# final.net
KiCad netlist of a schematic drawn in EasyEDA Pro
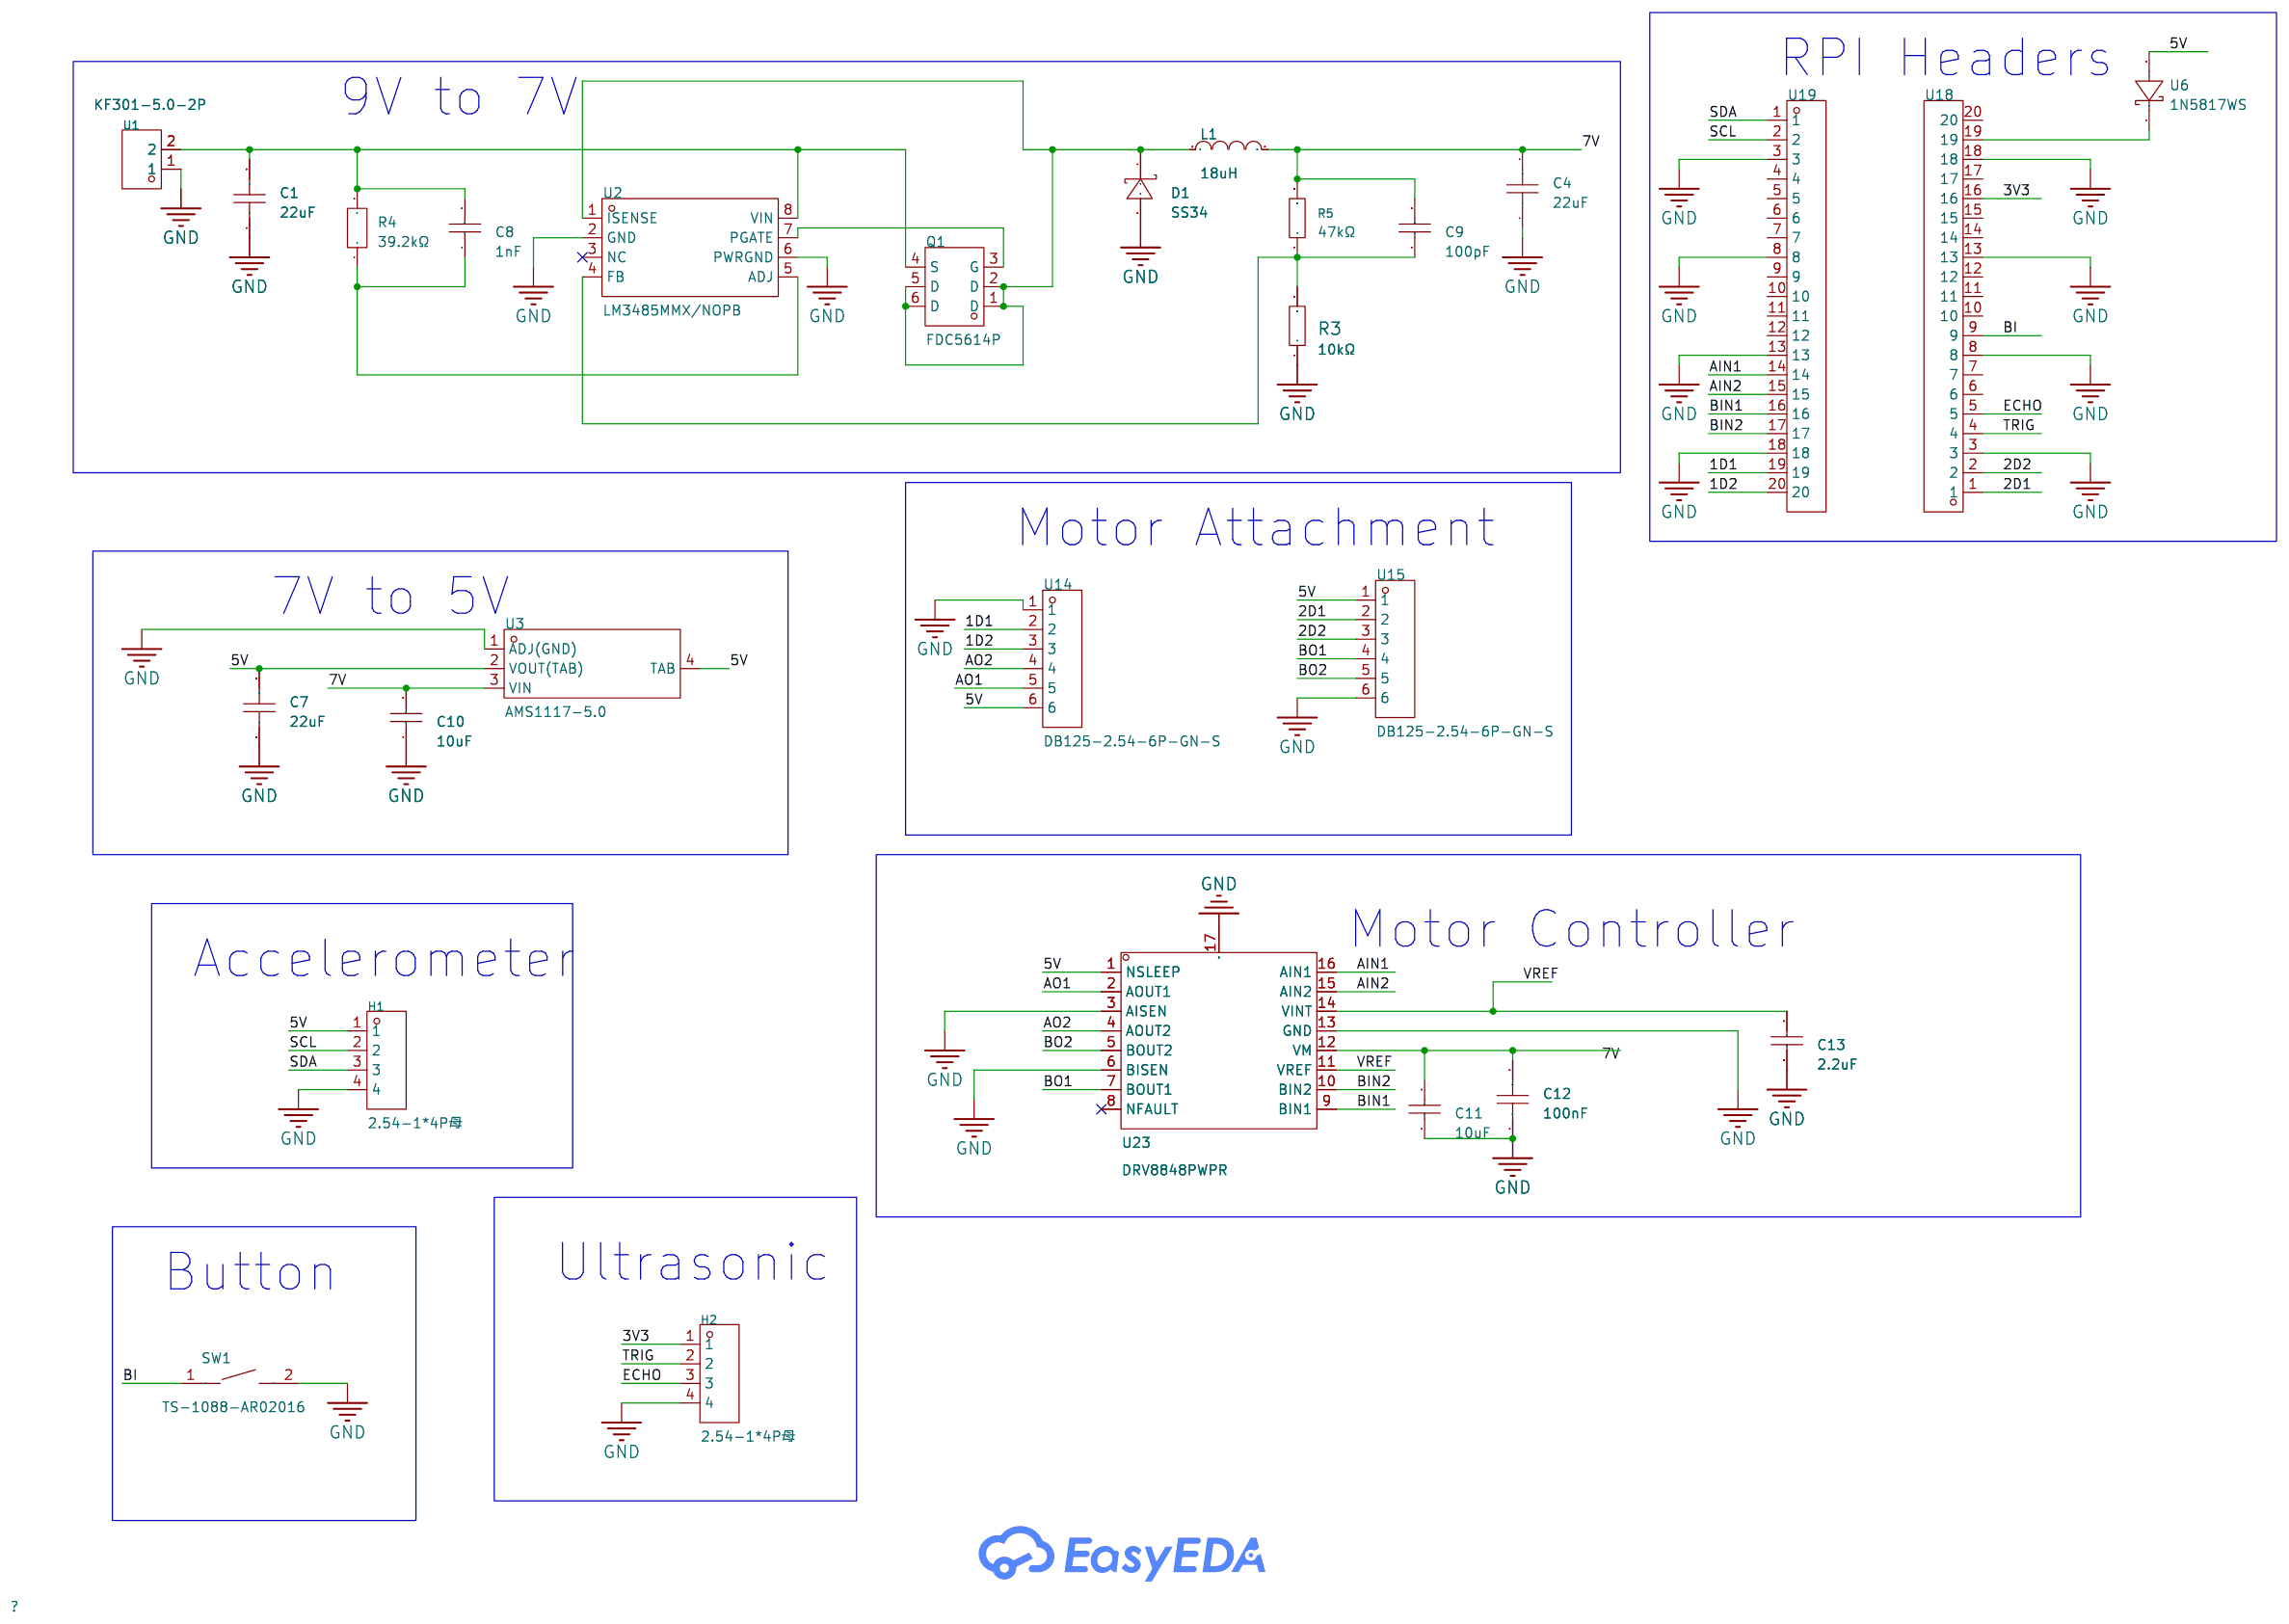
[diagram p0: schematic sheet]

(export (version "E")
  (design (tool "Eeschema 10.0.6"))
  (components
    (comp (ref "C1")
      (value "22uF")
      (footprint "easyedapro:C0603")
      (description "Capacitance:22uF Tolerance:±20% Tolerance:±20% Voltage Rating:6.3V Temperature Coefficient:X5R")
      (fields
        (field (name "Manufacturer Part") "CL10A226MQ8NRNC")
        (field (name "Manufacturer") "SAMSUNG(三星)")
      )
      (libsource (lib "easyedapro") (part "CL10A226MQ8NRNC"))
    )
    (comp (ref "C4")
      (value "22uF")
      (footprint "easyedapro:C0603")
      (description "Capacitance:22uF Tolerance:±20% Tolerance:±20% Voltage Rating:6.3V Temperature Coefficient:X5R")
      (fields
        (field (name "Manufacturer Part") "CL10A226MQ8NRNC")
        (field (name "Manufacturer") "SAMSUNG(三星)")
      )
      (libsource (lib "easyedapro") (part "CL10A226MQ8NRNC"))
    )
    (comp (ref "C7")
      (value "22uF")
      (footprint "easyedapro:C0603")
      (description "Capacitance:22uF Tolerance:±20% Tolerance:±20% Voltage Rating:6.3V Temperature Coefficient:X5R")
      (fields
        (field (name "Manufacturer Part") "CL10A226MQ8NRNC")
        (field (name "Manufacturer") "SAMSUNG(三星)")
      )
      (libsource (lib "easyedapro") (part "CL10A226MQ8NRNC"))
    )
    (comp (ref "C8")
      (value "1nF")
      (footprint "easyedapro:C0402")
      (description "Capacitance:1nF Tolerance:±10% Tolerance:±10% Voltage Rating:50V Temperature Coefficient:X7R")
      (fields (field (name "Manufacturer Part") "0402B102K500NT") (field (name "Manufacturer") "FH(风华)"))
      (libsource (lib "easyedapro") (part "0402B102K500NT"))
    )
    (comp (ref "C9")
      (value "100pF")
      (footprint "easyedapro:C0402")
      (fields (field (name "Manufacturer Part") "0402CG101J500NT") (field (name "Manufacturer") "FH(风华)"))
      (libsource (lib "easyedapro") (part "0402CG101J500NT"))
    )
    (comp (ref "C10")
      (value "10uF")
      (footprint "easyedapro:C1206")
      (description "Capacitance:10uF Tolerance:±10% Tolerance:±10% Voltage Rating:50V Temperature Coefficient:X5R")
      (fields
        (field (name "Manufacturer Part") "CL31A106KBHNNNE")
        (field (name "Manufacturer") "SAMSUNG(三星)")
      )
      (libsource (lib "easyedapro") (part "CL31A106KBHNNNE"))
    )
    (comp (ref "C11")
      (value "10uF")
      (footprint "easyedapro:C1206")
      (description "Capacitance:10uF Tolerance:±10% Tolerance:±10% Voltage Rating:50V Temperature Coefficient:X5R")
      (fields
        (field (name "Manufacturer Part") "CL31A106KBHNNNE")
        (field (name "Manufacturer") "SAMSUNG(三星)")
      )
      (libsource (lib "easyedapro") (part "CL31A106KBHNNNE"))
    )
    (comp (ref "C12")
      (value "100nF")
      (footprint "easyedapro:C0402")
      (description "Capacitance:100nF Tolerance:±10% Tolerance:±10% Voltage Rating:16V Temperature Coefficient:X7R")
      (fields
        (field (name "Manufacturer Part") "CL05B104KO5NNNC")
        (field (name "Manufacturer") "SAMSUNG(三星)")
      )
      (libsource (lib "easyedapro") (part "CL05B104KO5NNNC"))
    )
    (comp (ref "C13")
      (value "2.2uF")
      (footprint "easyedapro:C0603")
      (description "Capacitance:2.2uF Tolerance:±10% Tolerance:±10% Voltage Rating:16V Temperature Coefficient:X5R")
      (fields
        (field (name "Manufacturer Part") "CL10A225KO8NNNC")
        (field (name "Manufacturer") "SAMSUNG(三星)")
      )
      (libsource (lib "easyedapro") (part "CL10A225KO8NNNC"))
    )
    (comp (ref "D1")
      (value "SS34")
      (footprint "easyedapro:SMA_L4.3-W2.6-LS5.2-RD")
      (fields (field (name "Manufacturer") "MDD(辰达半导体)"))
      (libsource (lib "easyedapro") (part "SS34_C8678"))
    )
    (comp (ref "H1")
      (value "2.54-1*4P母")
      (footprint "easyedapro:HDR-TH_4P-P2.54-V-F")
      (fields (field (name "Manufacturer") "BOOMELE(博穆精密)"))
      (libsource (lib "easyedapro") (part "2.54-1*4P母"))
    )
    (comp (ref "H2")
      (value "2.54-1*4P母")
      (footprint "easyedapro:HDR-TH_4P-P2.54-V-F")
      (fields (field (name "Manufacturer") "BOOMELE(博穆精密)"))
      (libsource (lib "easyedapro") (part "2.54-1*4P母"))
    )
    (comp (ref "L1")
      (value "18uH")
      (footprint "easyedapro:IND-SMD_L4.0-W4.0_FNR4012S")
      (fields (field (name "Manufacturer Part") "FNR4012S180MT") (field (name "Manufacturer") "cjiang(长江微电)"))
      (libsource (lib "easyedapro") (part "FNR4012S180MT"))
    )
    (comp (ref "Q1")
      (value "FDC5614P")
      (footprint "easyedapro:SOT-23-6_L2.9-W1.6-P0.95-LS2.8-BR")
      (fields (field (name "Manufacturer") "MSKSEMI(美森科)"))
      (libsource (lib "easyedapro") (part "FDC5614P_C3029022"))
    )
    (comp (ref "R3")
      (value "10kΩ")
      (footprint "easyedapro:R0603")
      (fields
        (field (name "Manufacturer Part") "0603WAF1002T5E")
        (field (name "Manufacturer") "UNI-ROYAL(厚声)")
      )
      (libsource (lib "easyedapro") (part "0603WAF1002T5E"))
    )
    (comp (ref "R4")
      (value "39.2kΩ")
      (footprint "easyedapro:R0402")
      (fields (field (name "Manufacturer Part") "FRC0402F3922TS") (field (name "Manufacturer") "FOJAN(富捷)"))
      (libsource (lib "easyedapro") (part "FRC0402F3922TS"))
    )
    (comp (ref "R5")
      (value "47kΩ")
      (footprint "easyedapro:R0805")
      (fields
        (field (name "Manufacturer Part") "0805W8F4702T5E")
        (field (name "Manufacturer") "UNI-ROYAL(厚声)")
      )
      (libsource (lib "easyedapro") (part "0805W8F4702T5E"))
    )
    (comp (ref "SW1")
      (value "TS-1088-AR02016")
      (footprint "easyedapro:SW-SMD_L3.9-W3.0-P4.45")
      (fields (field (name "Manufacturer") "XUNPU(讯普)"))
      (libsource (lib "easyedapro") (part "TS-1088-AR02016"))
    )
    (comp (ref "U1")
      (value "KF301-5.0-2P")
      (footprint "easyedapro:CONN-TH_P5.00_KF301-5.0-2P")
      (fields (field (name "Manufacturer") "KEFA(科发)"))
      (libsource (lib "easyedapro") (part "KF301-5.0-2P"))
    )
    (comp (ref "U2")
      (value "LM3485MMX/NOPB")
      (footprint "easyedapro:VSSOP-8_L3.0-W3.0-P0.65-LS4.9-BL")
      (fields (field (name "Manufacturer") "TI(德州仪器)"))
      (libsource (lib "easyedapro") (part "LM3485MMX/NOPB"))
    )
    (comp (ref "U3")
      (value "AMS1117-5.0")
      (footprint "easyedapro:SOT-223_L6.7-W3.5-P2.30-BR")
      (fields (field (name "Manufacturer") "UMW(友台半导体)"))
      (libsource (lib "easyedapro") (part "AMS1117-5.0_C347223"))
    )
    (comp (ref "U6")
      (value "1N5817WS")
      (footprint "easyedapro:SOD-323_L1.7-W1.3-LS2.6-RD-1")
      (description "Reverse Voltage (Vr):20V Rectified Current:1A")
      (fields (field (name "Manufacturer") "Hottech(合科泰)"))
      (libsource (lib "easyedapro") (part "1N5817WS_C5190152"))
    )
    (comp (ref "U14")
      (value "DB125-2.54-6P-GN-S")
      (footprint "easyedapro:CONN-TH_DB125-2.54-6P-GN")
      (fields (field (name "Manufacturer") "DORABO(地博电气)"))
      (libsource (lib "easyedapro") (part "DB125-2.54-6P-GN"))
    )
    (comp (ref "U15")
      (value "DB125-2.54-6P-GN-S")
      (footprint "easyedapro:CONN-TH_DB125-2.54-6P-GN")
      (fields (field (name "Manufacturer") "DORABO(地博电气)"))
      (libsource (lib "easyedapro") (part "DB125-2.54-6P-GN"))
    )
    (comp (ref "U18")
      (value "ZX-PM2.54-1-20PY")
      (footprint "easyedapro:HDR-TH_20P-P2.54-V-F")
      (fields (field (name "Manufacturer") "Megastar(兆星)"))
      (libsource (lib "easyedapro") (part "ZX-PM2.54-1-20PY"))
    )
    (comp (ref "U19")
      (value "ZX-PM2.54-1-20PY")
      (footprint "easyedapro:HDR-TH_20P-P2.54-V-F")
      (fields (field (name "Manufacturer") "Megastar(兆星)"))
      (libsource (lib "easyedapro") (part "ZX-PM2.54-1-20PY"))
    )
    (comp (ref "U23")
      (value "DRV8848PWPR")
      (footprint "easyedapro:HTSSOP-16_L5.0-W4.4-P0.65-LS6.4-BL-EP")
      (fields (field (name "Manufacturer") "TI(德州仪器)"))
      (libsource (lib "easyedapro") (part "DRV8848PWPR"))
    )
  )
  (nets
    (net (code "1") (name "/1D1") (class "Default")
      (node (ref "U14") (pin "2") (pinfunction "2_2") (pintype "unspecified"))
      (node (ref "U19") (pin "19") (pinfunction "19_19") (pintype "unspecified"))
    )
    (net (code "2") (name "/1D2") (class "Default")
      (node (ref "U14") (pin "3") (pinfunction "3_3") (pintype "unspecified"))
      (node (ref "U19") (pin "20") (pinfunction "20_20") (pintype "unspecified"))
    )
    (net (code "3") (name "/2D1") (class "Default")
      (node (ref "U15") (pin "2") (pinfunction "2_2") (pintype "unspecified"))
      (node (ref "U18") (pin "1") (pinfunction "1_1") (pintype "unspecified"))
    )
    (net (code "4") (name "/2D2") (class "Default")
      (node (ref "U15") (pin "3") (pinfunction "3_3") (pintype "unspecified"))
      (node (ref "U18") (pin "2") (pinfunction "2_2") (pintype "unspecified"))
    )
    (net (code "5") (name "/3V3") (class "Default")
      (node (ref "H2") (pin "1") (pinfunction "1_1") (pintype "input"))
      (node (ref "U18") (pin "16") (pinfunction "16_16") (pintype "unspecified"))
    )
    (net (code "6") (name "/5V") (class "Default")
      (node (ref "C7") (pin "2") (pinfunction "2_2") (pintype "unspecified"))
      (node (ref "H1") (pin "1") (pinfunction "1_1") (pintype "input"))
      (node (ref "U14") (pin "6") (pinfunction "6_6") (pintype "unspecified"))
      (node (ref "U15") (pin "1") (pinfunction "1_1") (pintype "unspecified"))
      (node (ref "U23") (pin "1") (pinfunction "NSLEEP_1") (pintype "unspecified"))
      (node (ref "U3") (pin "2") (pinfunction "VOUT(TAB)_2") (pintype "unspecified"))
      (node (ref "U3") (pin "4") (pinfunction "TAB_4") (pintype "unspecified"))
      (node (ref "U6") (pin "2") (pinfunction "A_2") (pintype "unspecified"))
    )
    (net (code "7") (name "/7V") (class "Default")
      (node (ref "C10") (pin "2") (pinfunction "2_2") (pintype "input"))
      (node (ref "C11") (pin "2") (pinfunction "2_2") (pintype "input"))
      (node (ref "C12") (pin "2") (pinfunction "2_2") (pintype "unspecified"))
      (node (ref "C4") (pin "2") (pinfunction "2_2") (pintype "unspecified"))
      (node (ref "C9") (pin "2") (pinfunction "2_2") (pintype "input"))
      (node (ref "L1") (pin "2") (pinfunction "2_2") (pintype "unspecified"))
      (node (ref "R5") (pin "2") (pinfunction "2_2") (pintype "input"))
      (node (ref "U23") (pin "12") (pinfunction "VM_12") (pintype "unspecified"))
      (node (ref "U3") (pin "3") (pinfunction "VIN_3") (pintype "unspecified"))
    )
    (net (code "8") (name "/AIN1") (class "Default")
      (node (ref "U19") (pin "14") (pinfunction "14_14") (pintype "unspecified"))
      (node (ref "U23") (pin "16") (pinfunction "AIN1_16") (pintype "unspecified"))
    )
    (net (code "9") (name "/AIN2") (class "Default")
      (node (ref "U19") (pin "15") (pinfunction "15_15") (pintype "unspecified"))
      (node (ref "U23") (pin "15") (pinfunction "AIN2_15") (pintype "unspecified"))
    )
    (net (code "10") (name "/AO1") (class "Default")
      (node (ref "U14") (pin "5") (pinfunction "5_5") (pintype "unspecified"))
      (node (ref "U23") (pin "2") (pinfunction "AOUT1_2") (pintype "unspecified"))
    )
    (net (code "11") (name "/AO2") (class "Default")
      (node (ref "U14") (pin "4") (pinfunction "4_4") (pintype "unspecified"))
      (node (ref "U23") (pin "4") (pinfunction "AOUT2_4") (pintype "unspecified"))
    )
    (net (code "12") (name "/BI") (class "Default")
      (node (ref "SW1") (pin "1") (pinfunction "1_1") (pintype "unspecified"))
      (node (ref "U18") (pin "9") (pinfunction "9_9") (pintype "unspecified"))
    )
    (net (code "13") (name "/BIN1") (class "Default")
      (node (ref "U19") (pin "16") (pinfunction "16_16") (pintype "unspecified"))
      (node (ref "U23") (pin "9") (pinfunction "BIN1_9") (pintype "unspecified"))
    )
    (net (code "14") (name "/BIN2") (class "Default")
      (node (ref "U19") (pin "17") (pinfunction "17_17") (pintype "unspecified"))
      (node (ref "U23") (pin "10") (pinfunction "BIN2_10") (pintype "unspecified"))
    )
    (net (code "15") (name "/BO1") (class "Default")
      (node (ref "U15") (pin "4") (pinfunction "4_4") (pintype "unspecified"))
      (node (ref "U23") (pin "7") (pinfunction "BOUT1_7") (pintype "unspecified"))
    )
    (net (code "16") (name "/BO2") (class "Default")
      (node (ref "U15") (pin "5") (pinfunction "5_5") (pintype "unspecified"))
      (node (ref "U23") (pin "5") (pinfunction "BOUT2_5") (pintype "unspecified"))
    )
    (net (code "17") (name "/ECHO") (class "Default")
      (node (ref "H2") (pin "3") (pinfunction "3_3") (pintype "input"))
      (node (ref "U18") (pin "5") (pinfunction "5_5") (pintype "unspecified"))
    )
    (net (code "18") (name "/SCL") (class "Default")
      (node (ref "H1") (pin "2") (pinfunction "2_2") (pintype "input"))
      (node (ref "U19") (pin "2") (pinfunction "2_2") (pintype "unspecified"))
    )
    (net (code "19") (name "/SDA") (class "Default")
      (node (ref "H1") (pin "3") (pinfunction "3_3") (pintype "input"))
      (node (ref "U19") (pin "1") (pinfunction "1_1") (pintype "unspecified"))
    )
    (net (code "20") (name "/TRIG") (class "Default")
      (node (ref "H2") (pin "2") (pinfunction "2_2") (pintype "input"))
      (node (ref "U18") (pin "4") (pinfunction "4_4") (pintype "unspecified"))
    )
    (net (code "21") (name "/VREF") (class "Default")
      (node (ref "C13") (pin "2") (pinfunction "2_2") (pintype "input"))
      (node (ref "U23") (pin "11") (pinfunction "VREF_11") (pintype "unspecified"))
      (node (ref "U23") (pin "14") (pinfunction "VINT_14") (pintype "unspecified"))
    )
    (net (code "22") (name "GND") (class "Default")
      (node (ref "C1") (pin "1") (pinfunction "1_1") (pintype "unspecified"))
      (node (ref "C10") (pin "1") (pinfunction "1_1") (pintype "input"))
      (node (ref "C11") (pin "1") (pinfunction "1_1") (pintype "input"))
      (node (ref "C12") (pin "1") (pinfunction "1_1") (pintype "unspecified"))
      (node (ref "C13") (pin "1") (pinfunction "1_1") (pintype "input"))
      (node (ref "C4") (pin "1") (pinfunction "1_1") (pintype "unspecified"))
      (node (ref "C7") (pin "1") (pinfunction "1_1") (pintype "unspecified"))
      (node (ref "D1") (pin "2") (pinfunction "A_2") (pintype "unspecified"))
      (node (ref "H1") (pin "4") (pinfunction "4_4") (pintype "input"))
      (node (ref "H2") (pin "4") (pinfunction "4_4") (pintype "input"))
      (node (ref "R3") (pin "1") (pinfunction "1_1") (pintype "input"))
      (node (ref "SW1") (pin "2") (pinfunction "2_2") (pintype "unspecified"))
      (node (ref "U1") (pin "1") (pinfunction "1_1") (pintype "input"))
      (node (ref "U14") (pin "1") (pinfunction "1_1") (pintype "unspecified"))
      (node (ref "U15") (pin "6") (pinfunction "6_6") (pintype "unspecified"))
      (node (ref "U18") (pin "13") (pinfunction "13_13") (pintype "unspecified"))
      (node (ref "U18") (pin "18") (pinfunction "18_18") (pintype "unspecified"))
      (node (ref "U18") (pin "3") (pinfunction "3_3") (pintype "unspecified"))
      (node (ref "U18") (pin "8") (pinfunction "8_8") (pintype "unspecified"))
      (node (ref "U19") (pin "13") (pinfunction "13_13") (pintype "unspecified"))
      (node (ref "U19") (pin "18") (pinfunction "18_18") (pintype "unspecified"))
      (node (ref "U19") (pin "3") (pinfunction "3_3") (pintype "unspecified"))
      (node (ref "U19") (pin "8") (pinfunction "8_8") (pintype "unspecified"))
      (node (ref "U2") (pin "2") (pinfunction "GND_2") (pintype "unspecified"))
      (node (ref "U2") (pin "6") (pinfunction "PWRGND_6") (pintype "unspecified"))
      (node (ref "U23") (pin "13") (pinfunction "GND_13") (pintype "unspecified"))
      (node (ref "U23") (pin "17") (pinfunction "PAD_17") (pintype "unspecified"))
      (node (ref "U23") (pin "3") (pinfunction "AISEN_3") (pintype "unspecified"))
      (node (ref "U23") (pin "6") (pinfunction "BISEN_6") (pintype "unspecified"))
      (node (ref "U3") (pin "1") (pinfunction "ADJ(GND)_1") (pintype "unspecified"))
    )
    (net (code "23") (name "Net-(D1-K)") (class "Default")
      (node (ref "D1") (pin "1") (pinfunction "K_1") (pintype "unspecified"))
      (node (ref "L1") (pin "1") (pinfunction "1_1") (pintype "unspecified"))
      (node (ref "Q1") (pin "1") (pinfunction "D_1") (pintype "unspecified"))
      (node (ref "Q1") (pin "2") (pinfunction "D_2") (pintype "unspecified"))
      (node (ref "Q1") (pin "5") (pinfunction "D_5") (pintype "unspecified"))
      (node (ref "Q1") (pin "6") (pinfunction "D_6") (pintype "unspecified"))
      (node (ref "U2") (pin "1") (pinfunction "ISENSE_1") (pintype "unspecified"))
    )
    (net (code "24") (name "Net-(Q1-G)") (class "Default")
      (node (ref "Q1") (pin "3") (pinfunction "G_3") (pintype "unspecified"))
      (node (ref "U2") (pin "7") (pinfunction "PGATE_7") (pintype "unspecified"))
    )
    (net (code "25") (name "Net-(Q1-S)") (class "Default")
      (node (ref "C1") (pin "2") (pinfunction "2_2") (pintype "unspecified"))
      (node (ref "C8") (pin "2") (pinfunction "2_2") (pintype "input"))
      (node (ref "Q1") (pin "4") (pinfunction "S_4") (pintype "unspecified"))
      (node (ref "R4") (pin "2") (pinfunction "2_2") (pintype "unspecified"))
      (node (ref "U1") (pin "2") (pinfunction "2_2") (pintype "input"))
      (node (ref "U2") (pin "8") (pinfunction "VIN_8") (pintype "unspecified"))
    )
    (net (code "26") (name "Net-(U2-ADJ)") (class "Default")
      (node (ref "C8") (pin "1") (pinfunction "1_1") (pintype "input"))
      (node (ref "R4") (pin "1") (pinfunction "1_1") (pintype "unspecified"))
      (node (ref "U2") (pin "5") (pinfunction "ADJ_5") (pintype "unspecified"))
    )
    (net (code "27") (name "Net-(U2-FB)") (class "Default")
      (node (ref "C9") (pin "1") (pinfunction "1_1") (pintype "input"))
      (node (ref "R3") (pin "2") (pinfunction "2_2") (pintype "input"))
      (node (ref "R5") (pin "1") (pinfunction "1_1") (pintype "input"))
      (node (ref "U2") (pin "4") (pinfunction "FB_4") (pintype "unspecified"))
    )
    (net (code "28") (name "Net-(U6-C)") (class "Default")
      (node (ref "U18") (pin "19") (pinfunction "19_19") (pintype "unspecified"))
      (node (ref "U6") (pin "1") (pinfunction "C_1") (pintype "unspecified"))
    )
    (net (code "29") (name "unconnected-(U2-NC-Pad3)") (class "Default")
      (node (ref "U2") (pin "3") (pinfunction "NC_3") (pintype "unspecified+no_connect"))
    )
    (net (code "30") (name "unconnected-(U18-Pad6)") (class "Default")
      (node (ref "U18") (pin "6") (pinfunction "6_6") (pintype "unspecified"))
    )
    (net (code "31") (name "unconnected-(U18-Pad7)") (class "Default")
      (node (ref "U18") (pin "7") (pinfunction "7_7") (pintype "unspecified"))
    )
    (net (code "32") (name "unconnected-(U18-Pad10)") (class "Default")
      (node (ref "U18") (pin "10") (pinfunction "10_10") (pintype "unspecified"))
    )
    (net (code "33") (name "unconnected-(U18-Pad11)") (class "Default")
      (node (ref "U18") (pin "11") (pinfunction "11_11") (pintype "unspecified"))
    )
    (net (code "34") (name "unconnected-(U18-Pad12)") (class "Default")
      (node (ref "U18") (pin "12") (pinfunction "12_12") (pintype "unspecified"))
    )
    (net (code "35") (name "unconnected-(U18-Pad14)") (class "Default")
      (node (ref "U18") (pin "14") (pinfunction "14_14") (pintype "unspecified"))
    )
    (net (code "36") (name "unconnected-(U18-Pad15)") (class "Default")
      (node (ref "U18") (pin "15") (pinfunction "15_15") (pintype "unspecified"))
    )
    (net (code "37") (name "unconnected-(U18-Pad17)") (class "Default")
      (node (ref "U18") (pin "17") (pinfunction "17_17") (pintype "unspecified"))
    )
    (net (code "38") (name "unconnected-(U18-Pad20)") (class "Default")
      (node (ref "U18") (pin "20") (pinfunction "20_20") (pintype "unspecified"))
    )
    (net (code "39") (name "unconnected-(U19-Pad4)") (class "Default")
      (node (ref "U19") (pin "4") (pinfunction "4_4") (pintype "unspecified"))
    )
    (net (code "40") (name "unconnected-(U19-Pad5)") (class "Default")
      (node (ref "U19") (pin "5") (pinfunction "5_5") (pintype "unspecified"))
    )
    (net (code "41") (name "unconnected-(U19-Pad6)") (class "Default")
      (node (ref "U19") (pin "6") (pinfunction "6_6") (pintype "unspecified"))
    )
    (net (code "42") (name "unconnected-(U19-Pad7)") (class "Default")
      (node (ref "U19") (pin "7") (pinfunction "7_7") (pintype "unspecified"))
    )
    (net (code "43") (name "unconnected-(U19-Pad9)") (class "Default")
      (node (ref "U19") (pin "9") (pinfunction "9_9") (pintype "unspecified"))
    )
    (net (code "44") (name "unconnected-(U19-Pad10)") (class "Default")
      (node (ref "U19") (pin "10") (pinfunction "10_10") (pintype "unspecified"))
    )
    (net (code "45") (name "unconnected-(U19-Pad11)") (class "Default")
      (node (ref "U19") (pin "11") (pinfunction "11_11") (pintype "unspecified"))
    )
    (net (code "46") (name "unconnected-(U19-Pad12)") (class "Default")
      (node (ref "U19") (pin "12") (pinfunction "12_12") (pintype "unspecified"))
    )
    (net (code "47") (name "unconnected-(U23-NFAULT-Pad8)") (class "Default")
      (node (ref "U23") (pin "8") (pinfunction "NFAULT_8") (pintype "unspecified+no_connect"))
    )
  )
)
